# Squematico2_0.net
KiCad netlist of a schematic drawn in EAGLE
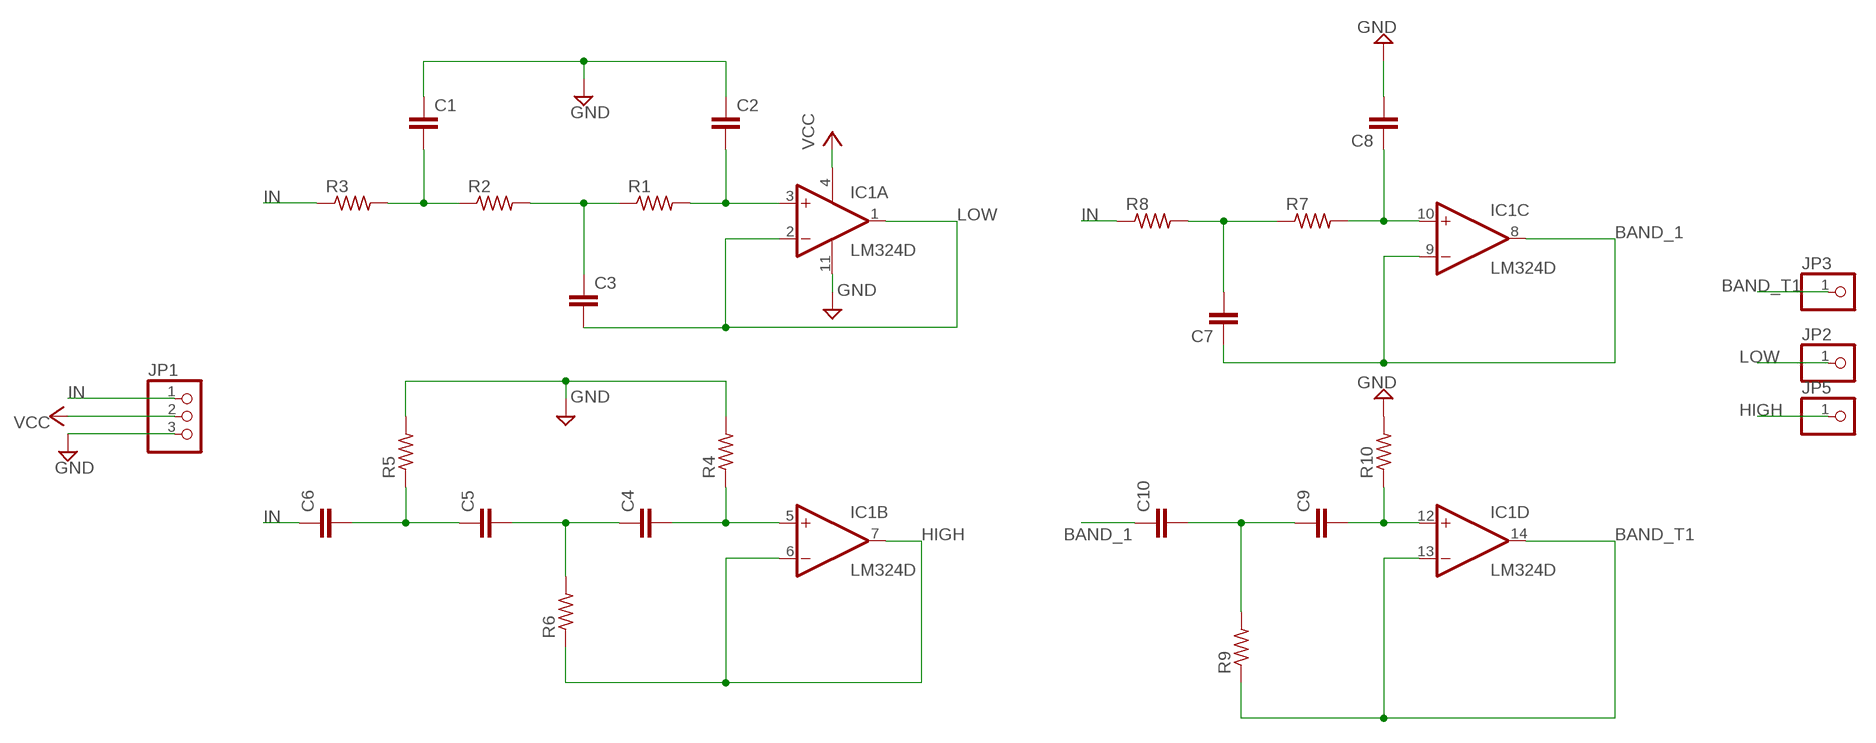
[diagram p0: schematic, sheet 1]

(export (version "E")
  (design (tool "Eeschema 10.0.6"))
  (components
    (comp (ref "C1")
      (value "C-EU025-025X050")
      (footprint "eagle-import:C025-025X050")
      (libsource (lib "eagle-import") (part "C-EU025-025X050"))
    )
    (comp (ref "C2")
      (value "C-EU025-025X050")
      (footprint "eagle-import:C025-025X050")
      (libsource (lib "eagle-import") (part "C-EU025-025X050"))
    )
    (comp (ref "C3")
      (value "C-EU025-025X050")
      (footprint "eagle-import:C025-025X050")
      (libsource (lib "eagle-import") (part "C-EU025-025X050"))
    )
    (comp (ref "C4")
      (value "C-EU025-025X050")
      (footprint "eagle-import:C025-025X050")
      (libsource (lib "eagle-import") (part "C-EU025-025X050"))
    )
    (comp (ref "C5")
      (value "C-EU025-025X050")
      (footprint "eagle-import:C025-025X050")
      (libsource (lib "eagle-import") (part "C-EU025-025X050"))
    )
    (comp (ref "C6")
      (value "C-EU025-025X050")
      (footprint "eagle-import:C025-025X050")
      (libsource (lib "eagle-import") (part "C-EU025-025X050"))
    )
    (comp (ref "C7")
      (value "C-EU025-025X050")
      (footprint "eagle-import:C025-025X050")
      (libsource (lib "eagle-import") (part "C-EU025-025X050"))
    )
    (comp (ref "C8")
      (value "C-EU025-025X050")
      (footprint "eagle-import:C025-025X050")
      (libsource (lib "eagle-import") (part "C-EU025-025X050"))
    )
    (comp (ref "C9")
      (value "C-EU025-025X050")
      (footprint "eagle-import:C025-025X050")
      (libsource (lib "eagle-import") (part "C-EU025-025X050"))
    )
    (comp (ref "C10")
      (value "C-EU025-025X050")
      (footprint "eagle-import:C025-025X050")
      (libsource (lib "eagle-import") (part "C-EU025-025X050"))
    )
    (comp (ref "IC1")
      (value "LM324D")
      (footprint "eagle-import:SO14")
      (libsource (lib "eagle-import") (part "LM324D"))
    )
    (comp (ref "JP1")
      (value "PINHD-1X3")
      (footprint "eagle-import:1X03")
      (libsource (lib "eagle-import") (part "PINHD-1X3"))
    )
    (comp (ref "JP2")
      (value "PINHD-1X1")
      (footprint "eagle-import:1X01")
      (libsource (lib "eagle-import") (part "PINHD-1X1"))
    )
    (comp (ref "JP3")
      (value "PINHD-1X1")
      (footprint "eagle-import:1X01")
      (libsource (lib "eagle-import") (part "PINHD-1X1"))
    )
    (comp (ref "JP5")
      (value "PINHD-1X1")
      (footprint "eagle-import:1X01")
      (libsource (lib "eagle-import") (part "PINHD-1X1"))
    )
    (comp (ref "R1")
      (value "R-US_0204/7")
      (footprint "eagle-import:0204_7")
      (libsource (lib "eagle-import") (part "R-US_0204/7"))
    )
    (comp (ref "R2")
      (value "R-US_0204/7")
      (footprint "eagle-import:0204_7")
      (libsource (lib "eagle-import") (part "R-US_0204/7"))
    )
    (comp (ref "R3")
      (value "R-US_0204/7")
      (footprint "eagle-import:0204_7")
      (libsource (lib "eagle-import") (part "R-US_0204/7"))
    )
    (comp (ref "R4")
      (value "R-US_0204/7")
      (footprint "eagle-import:0204_7")
      (libsource (lib "eagle-import") (part "R-US_0204/7"))
    )
    (comp (ref "R5")
      (value "R-US_0204/7")
      (footprint "eagle-import:0204_7")
      (libsource (lib "eagle-import") (part "R-US_0204/7"))
    )
    (comp (ref "R6")
      (value "R-US_0204/7")
      (footprint "eagle-import:0204_7")
      (libsource (lib "eagle-import") (part "R-US_0204/7"))
    )
    (comp (ref "R7")
      (value "R-US_0204/7")
      (footprint "eagle-import:0204_7")
      (libsource (lib "eagle-import") (part "R-US_0204/7"))
    )
    (comp (ref "R8")
      (value "R-US_0204/7")
      (footprint "eagle-import:0204_7")
      (libsource (lib "eagle-import") (part "R-US_0204/7"))
    )
    (comp (ref "R9")
      (value "R-US_0204/7")
      (footprint "eagle-import:0204_7")
      (libsource (lib "eagle-import") (part "R-US_0204/7"))
    )
    (comp (ref "R10")
      (value "R-US_0204/7")
      (footprint "eagle-import:0204_7")
      (libsource (lib "eagle-import") (part "R-US_0204/7"))
    )
  )
  (nets
    (net (code "1") (name "/BAND_1") (class "Default")
      (node (ref "C10") (pin "1") (pinfunction "1_1") (pintype "passive"))
      (node (ref "C7") (pin "1") (pinfunction "1_1") (pintype "passive"))
      (node (ref "IC1") (pin "8") (pinfunction "OUT_8") (pintype "output"))
      (node (ref "IC1") (pin "9") (pinfunction "-IN_9") (pintype "input"))
    )
    (net (code "2") (name "/BAND_T1") (class "Default")
      (node (ref "IC1") (pin "13") (pinfunction "-IN_13") (pintype "input"))
      (node (ref "IC1") (pin "14") (pinfunction "OUT_14") (pintype "output"))
      (node (ref "JP3") (pin "1") (pinfunction "1_1") (pintype "passive"))
      (node (ref "R9") (pin "1") (pinfunction "1_1") (pintype "passive"))
    )
    (net (code "3") (name "/HIGH") (class "Default")
      (node (ref "IC1") (pin "6") (pinfunction "-IN_6") (pintype "input"))
      (node (ref "IC1") (pin "7") (pinfunction "OUT_7") (pintype "output"))
      (node (ref "JP5") (pin "1") (pinfunction "1_1") (pintype "passive"))
      (node (ref "R6") (pin "1") (pinfunction "1_1") (pintype "passive"))
    )
    (net (code "4") (name "/IN") (class "Default")
      (node (ref "C6") (pin "1") (pinfunction "1_1") (pintype "passive"))
      (node (ref "JP1") (pin "1") (pinfunction "1_1") (pintype "passive"))
      (node (ref "R3") (pin "1") (pinfunction "1_1") (pintype "passive"))
      (node (ref "R8") (pin "1") (pinfunction "1_1") (pintype "passive"))
    )
    (net (code "5") (name "/LOW") (class "Default")
      (node (ref "C3") (pin "2") (pinfunction "2_2") (pintype "passive"))
      (node (ref "IC1") (pin "1") (pinfunction "OUT_1") (pintype "output"))
      (node (ref "IC1") (pin "2") (pinfunction "-IN_2") (pintype "input"))
      (node (ref "JP2") (pin "1") (pinfunction "1_1") (pintype "passive"))
    )
    (net (code "6") (name "GND") (class "Default")
      (node (ref "C1") (pin "1") (pinfunction "1_1") (pintype "passive"))
      (node (ref "C2") (pin "1") (pinfunction "1_1") (pintype "passive"))
      (node (ref "C8") (pin "2") (pinfunction "2_2") (pintype "passive"))
      (node (ref "IC1") (pin "11") (pinfunction "V-_11") (pintype "power_in"))
      (node (ref "JP1") (pin "3") (pinfunction "3_3") (pintype "passive"))
      (node (ref "R10") (pin "2") (pinfunction "2_2") (pintype "passive"))
      (node (ref "R4") (pin "2") (pinfunction "2_2") (pintype "passive"))
      (node (ref "R5") (pin "2") (pinfunction "2_2") (pintype "passive"))
    )
    (net (code "7") (name "Net-(C1-Pad2)") (class "Default")
      (node (ref "C1") (pin "2") (pinfunction "2_2") (pintype "passive"))
      (node (ref "R2") (pin "1") (pinfunction "1_1") (pintype "passive"))
      (node (ref "R3") (pin "2") (pinfunction "2_2") (pintype "passive"))
    )
    (net (code "8") (name "Net-(C3-Pad1)") (class "Default")
      (node (ref "C3") (pin "1") (pinfunction "1_1") (pintype "passive"))
      (node (ref "R1") (pin "1") (pinfunction "1_1") (pintype "passive"))
      (node (ref "R2") (pin "2") (pinfunction "2_2") (pintype "passive"))
    )
    (net (code "9") (name "Net-(C4-Pad1)") (class "Default")
      (node (ref "C4") (pin "1") (pinfunction "1_1") (pintype "passive"))
      (node (ref "C5") (pin "2") (pinfunction "2_2") (pintype "passive"))
      (node (ref "R6") (pin "2") (pinfunction "2_2") (pintype "passive"))
    )
    (net (code "10") (name "Net-(C5-Pad1)") (class "Default")
      (node (ref "C5") (pin "1") (pinfunction "1_1") (pintype "passive"))
      (node (ref "C6") (pin "2") (pinfunction "2_2") (pintype "passive"))
      (node (ref "R5") (pin "1") (pinfunction "1_1") (pintype "passive"))
    )
    (net (code "11") (name "Net-(C7-Pad2)") (class "Default")
      (node (ref "C7") (pin "2") (pinfunction "2_2") (pintype "passive"))
      (node (ref "R7") (pin "1") (pinfunction "1_1") (pintype "passive"))
      (node (ref "R8") (pin "2") (pinfunction "2_2") (pintype "passive"))
    )
    (net (code "12") (name "Net-(C10-Pad2)") (class "Default")
      (node (ref "C10") (pin "2") (pinfunction "2_2") (pintype "passive"))
      (node (ref "C9") (pin "1") (pinfunction "1_1") (pintype "passive"))
      (node (ref "R9") (pin "2") (pinfunction "2_2") (pintype "passive"))
    )
    (net (code "13") (name "Net-(IC1A-+IN)") (class "Default")
      (node (ref "C2") (pin "2") (pinfunction "2_2") (pintype "passive"))
      (node (ref "IC1") (pin "3") (pinfunction "+IN_3") (pintype "input"))
      (node (ref "R1") (pin "2") (pinfunction "2_2") (pintype "passive"))
    )
    (net (code "14") (name "Net-(IC1B-+IN)") (class "Default")
      (node (ref "C4") (pin "2") (pinfunction "2_2") (pintype "passive"))
      (node (ref "IC1") (pin "5") (pinfunction "+IN_5") (pintype "input"))
      (node (ref "R4") (pin "1") (pinfunction "1_1") (pintype "passive"))
    )
    (net (code "15") (name "Net-(IC1C-+IN)") (class "Default")
      (node (ref "C8") (pin "1") (pinfunction "1_1") (pintype "passive"))
      (node (ref "IC1") (pin "10") (pinfunction "+IN_10") (pintype "input"))
      (node (ref "R7") (pin "2") (pinfunction "2_2") (pintype "passive"))
    )
    (net (code "16") (name "Net-(IC1D-+IN)") (class "Default")
      (node (ref "C9") (pin "2") (pinfunction "2_2") (pintype "passive"))
      (node (ref "IC1") (pin "12") (pinfunction "+IN_12") (pintype "input"))
      (node (ref "R10") (pin "1") (pinfunction "1_1") (pintype "passive"))
    )
    (net (code "17") (name "VCC") (class "Default")
      (node (ref "IC1") (pin "4") (pinfunction "V+_4") (pintype "power_in"))
      (node (ref "JP1") (pin "2") (pinfunction "2_2") (pintype "passive"))
    )
  )
)
